# LCD.net
KiCad netlist of a schematic drawn in Altium Designer
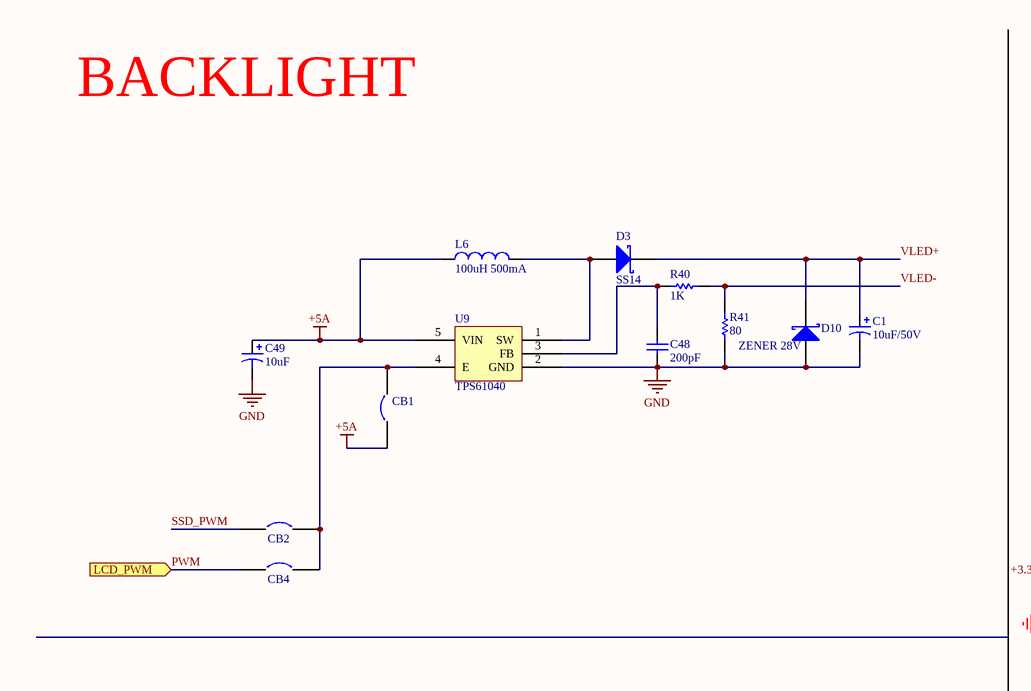
[diagram p0: LCD.SchDoc, left]
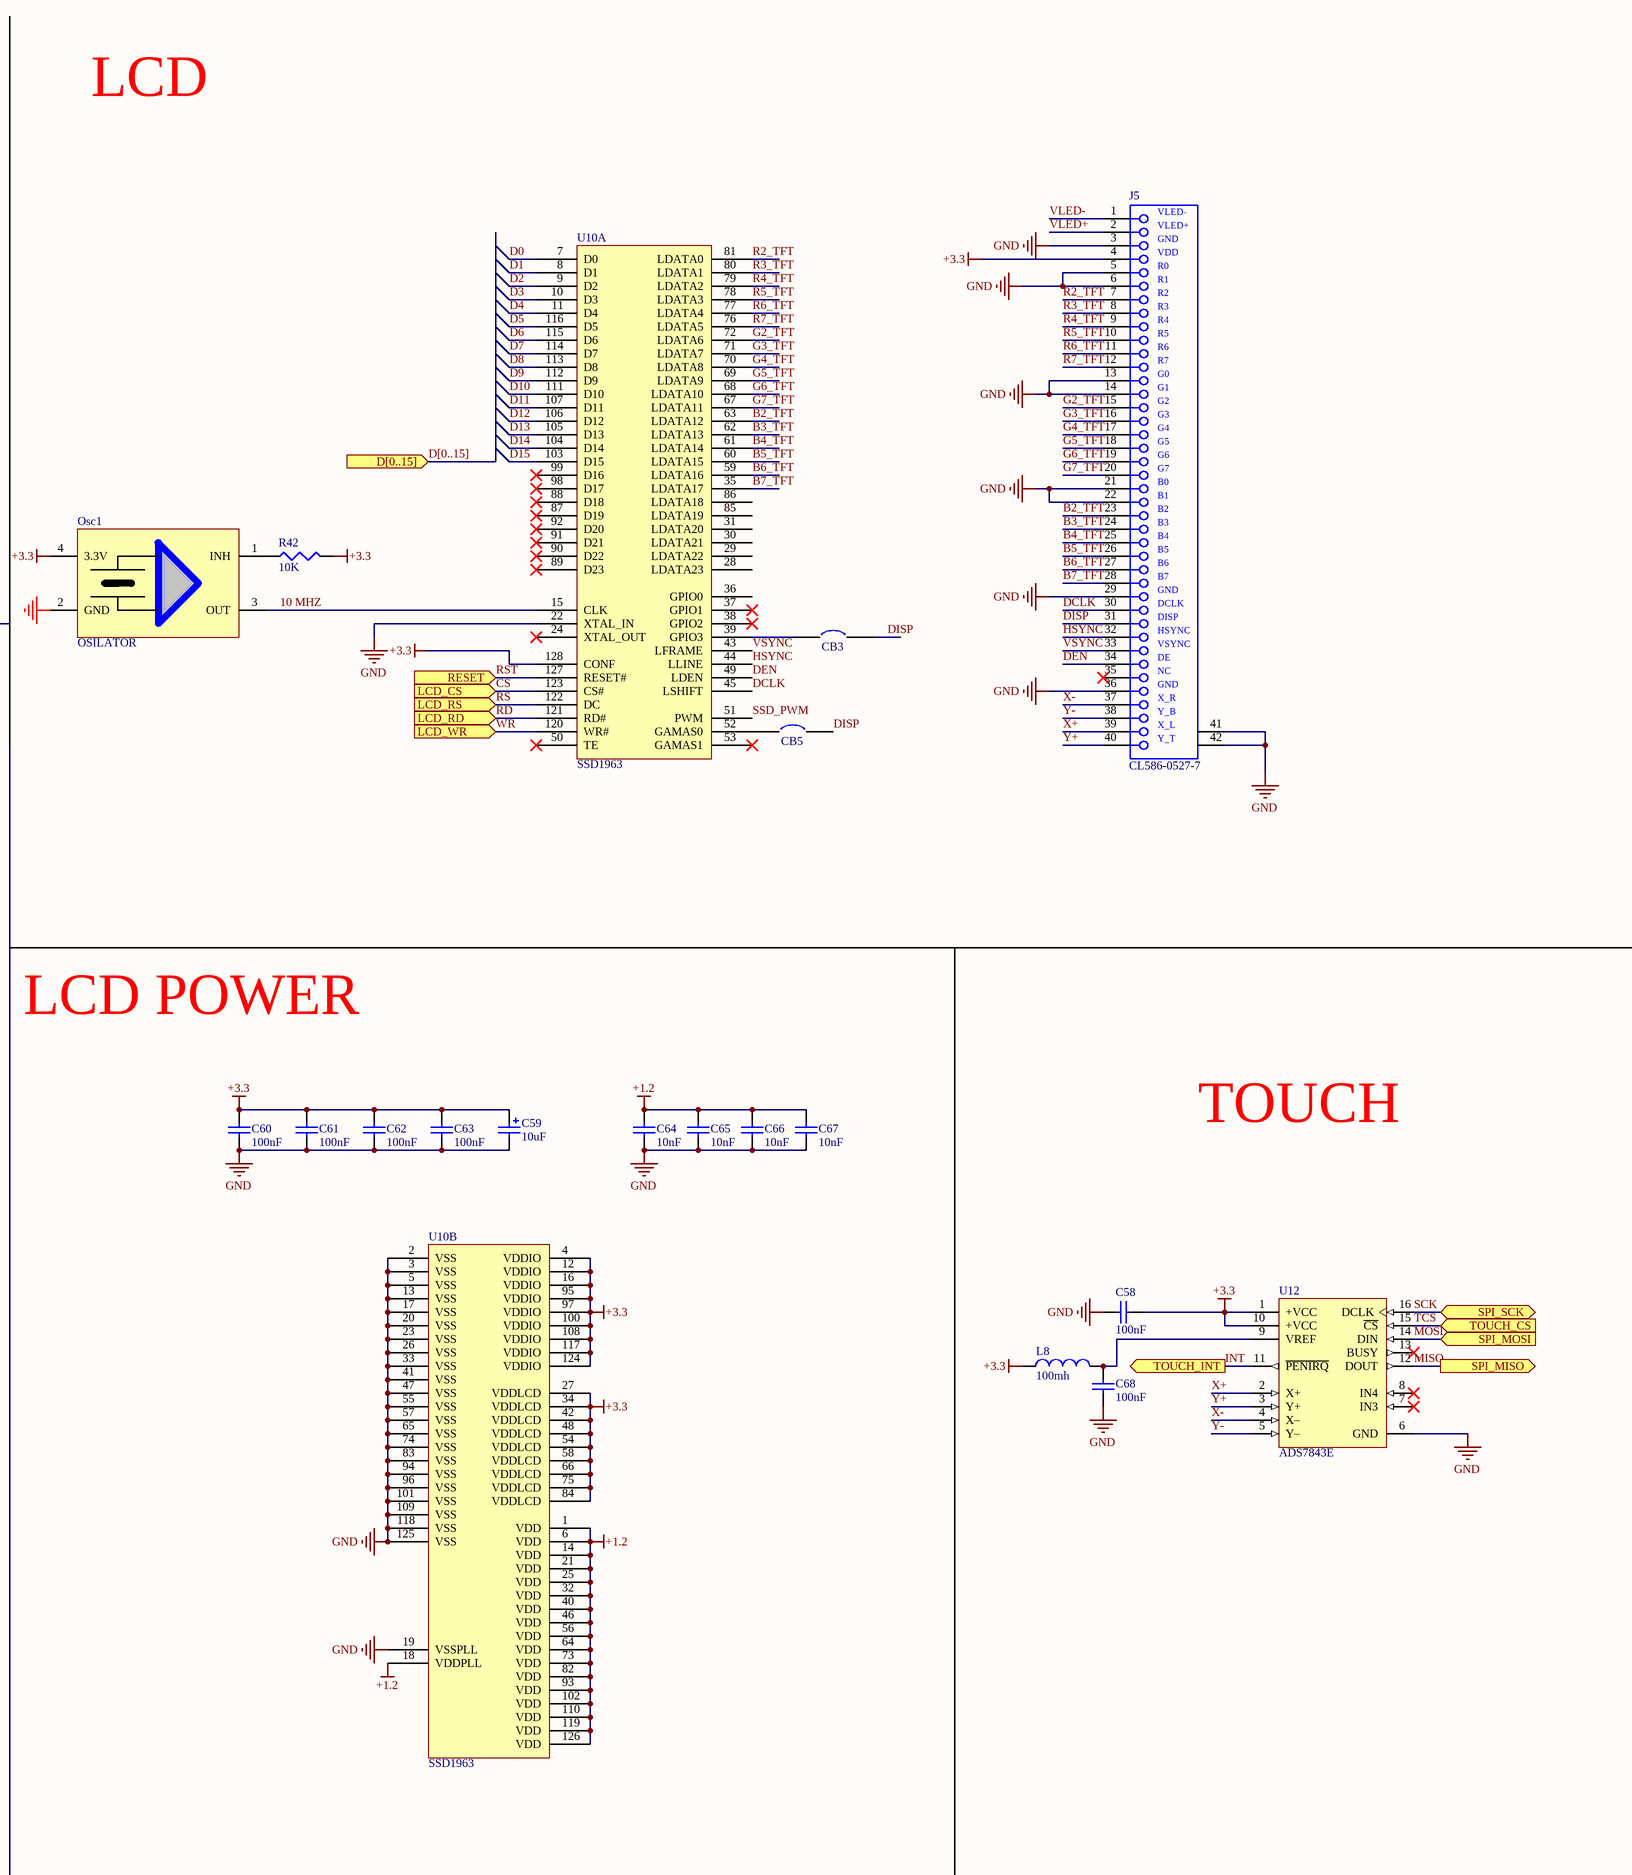
[diagram p1: LCD.SchDoc, right]

(export (version "E")
  (design (tool "Eeschema 10.0.6"))
  (components
    (comp (ref "C1")
      (value "10uF/50V")
      (footprint "CAP1050")
      (description "Polarized Capacitor (Radial)")
      (fields (field (name "PUBLISHER") "Altium Limited"))
      (libsource (lib "") (part "Cap Pol1_1"))
    )
    (comp (ref "C48")
      (value "200pF")
      (footprint "1206")
      (description "Capacitor (Semiconductor SIM Model)")
      (fields (field (name "PUBLISHER") "Altium Limited"))
      (libsource (lib "Miscellaneous Devices") (part "Cap Semi"))
    )
    (comp (ref "C49")
      (value "10uF")
      (footprint "CAP1016")
      (description "Polarized Capacitor (Radial)")
      (fields (field (name "PUBLISHER") "Altium Limited"))
      (libsource (lib "") (part "Cap Pol1_1"))
    )
    (comp (ref "C58")
      (value "100nF")
      (footprint "1206")
      (description "Capacitor")
      (fields (field (name "PUBLISHER") "Altium Limited"))
      (libsource (lib "Miscellaneous Devices") (part "Cap"))
    )
    (comp (ref "C59")
      (value "10uF")
      (footprint "CAP1016")
      (description "Polarized Capacitor (Radial)")
      (fields (field (name "PUBLISHER") "Altium Limited"))
      (libsource (lib "Miscellaneous Devices") (part "Cap Pol1"))
    )
    (comp (ref "C60")
      (value "100nF")
      (footprint "0805")
      (description "Capacitor")
      (fields (field (name "PUBLISHER") "Altium Limited"))
      (libsource (lib "Miscellaneous Devices") (part "Cap"))
    )
    (comp (ref "C61")
      (value "100nF")
      (footprint "0805")
      (description "Capacitor")
      (fields (field (name "PUBLISHER") "Altium Limited"))
      (libsource (lib "Miscellaneous Devices") (part "Cap"))
    )
    (comp (ref "C62")
      (value "100nF")
      (footprint "0805")
      (description "Capacitor")
      (fields (field (name "PUBLISHER") "Altium Limited"))
      (libsource (lib "Miscellaneous Devices") (part "Cap"))
    )
    (comp (ref "C63")
      (value "100nF")
      (footprint "0805")
      (description "Capacitor")
      (fields (field (name "PUBLISHER") "Altium Limited"))
      (libsource (lib "Miscellaneous Devices") (part "Cap"))
    )
    (comp (ref "C64")
      (value "10nF")
      (footprint "0805")
      (description "Capacitor")
      (fields (field (name "PUBLISHER") "Altium Limited"))
      (libsource (lib "Miscellaneous Devices") (part "Cap"))
    )
    (comp (ref "C65")
      (value "10nF")
      (footprint "0805")
      (description "Capacitor")
      (fields (field (name "PUBLISHER") "Altium Limited"))
      (libsource (lib "Miscellaneous Devices") (part "Cap"))
    )
    (comp (ref "C66")
      (value "10nF")
      (footprint "0805")
      (description "Capacitor")
      (fields (field (name "PUBLISHER") "Altium Limited"))
      (libsource (lib "Miscellaneous Devices") (part "Cap"))
    )
    (comp (ref "C67")
      (value "10nF")
      (footprint "0805")
      (description "Capacitor")
      (fields (field (name "PUBLISHER") "Altium Limited"))
      (libsource (lib "Miscellaneous Devices") (part "Cap"))
    )
    (comp (ref "C68")
      (value "100nF")
      (footprint "1206")
      (description "Capacitor")
      (fields (field (name "PUBLISHER") "Altium Limited"))
      (libsource (lib "Miscellaneous Devices") (part "Cap"))
    )
    (comp (ref "CB1")
      (value "JUMPER")
      (footprint "0805")
      (description "Circuit Breaker")
      (fields (field (name "PUBLISHER") "Altium Limited"))
      (libsource (lib "Miscellaneous Devices") (part "Circuit Breaker"))
    )
    (comp (ref "CB2")
      (value "JUMPER")
      (footprint "0805")
      (description "Circuit Breaker")
      (fields (field (name "PUBLISHER") "Altium Limited"))
      (libsource (lib "Miscellaneous Devices") (part "Circuit Breaker"))
    )
    (comp (ref "CB3")
      (value "JUMPER")
      (footprint "0805")
      (description "Circuit Breaker")
      (fields (field (name "PUBLISHER") "Altium Limited"))
      (libsource (lib "Miscellaneous Devices") (part "Circuit Breaker"))
    )
    (comp (ref "CB4")
      (value "JUMPER")
      (footprint "0805")
      (description "Circuit Breaker")
      (fields (field (name "PUBLISHER") "Altium Limited"))
      (libsource (lib "Miscellaneous Devices") (part "Circuit Breaker"))
    )
    (comp (ref "CB5")
      (value "JUMPER")
      (footprint "0805")
      (description "Circuit Breaker")
      (fields (field (name "PUBLISHER") "Altium Limited"))
      (libsource (lib "Miscellaneous Devices") (part "Circuit Breaker"))
    )
    (comp (ref "D3")
      (value "SS14")
      (footprint "1N4007")
      (description "Schottky Diode")
      (fields (field (name "PUBLISHER") "Altium Limited"))
      (libsource (lib "Miscellaneous Devices") (part "D Schottky"))
    )
    (comp (ref "D10")
      (value "ZENER 28V")
      (footprint "1N4007")
      (description "Schottky Diode")
      (fields (field (name "PUBLISHER") "Altium Limited"))
      (libsource (lib "Miscellaneous Devices") (part "D Schottky"))
    )
    (comp (ref "J5")
      (value "CL586-0527-7")
      (footprint "FH40SB")
      (description "FH12 Series, \"Flip-Lock\" SMT/ZIF FFC/FPC Connector - 0.5mm Spaced Bottom Contact")
      (fields (field (name "PUBLISHER") "Altium Limited"))
      (libsource (lib "Schlib1") (part "CL586-0527-7"))
    )
    (comp (ref "L6")
      (value "100uH 500mA")
      (footprint "Inductorsmd")
      (description "Inductor")
      (fields (field (name "PUBLISHER") "Altium Limited"))
      (libsource (lib "Miscellaneous Devices") (part "Inductor"))
    )
    (comp (ref "L8")
      (value "100mh")
      (footprint "L1206")
      (description "Inductor")
      (fields (field (name "PUBLISHER") "Altium Limited"))
      (libsource (lib "Miscellaneous Devices") (part "Inductor"))
    )
    (comp (ref "Osc1")
      (value "OSILATOR")
      (footprint "XTAL_5X7")
      (libsource (lib "New Lib") (part "OSILATOR"))
    )
    (comp (ref "R40")
      (value "1K")
      (footprint "1206")
      (description "Resistor")
      (fields (field (name "PUBLISHER") "Altium Limited"))
      (libsource (lib "Miscellaneous Devices") (part "Res1"))
    )
    (comp (ref "R41")
      (value "80")
      (footprint "1206")
      (description "Resistor")
      (fields (field (name "PUBLISHER") "Altium Limited"))
      (libsource (lib "Miscellaneous Devices") (part "Res1"))
    )
    (comp (ref "R42")
      (value "10K")
      (footprint "1206")
      (description "Resistor")
      (fields (field (name "PUBLISHER") "Altium Limited"))
      (libsource (lib "Miscellaneous Devices") (part "Res3"))
    )
    (comp (ref "U9")
      (value "TPS61040")
      (footprint "SOT-23-5L")
      (description "Backlight Regulagtor")
      (libsource (lib "Schlib1") (part "TPS61040"))
    )
    (comp (ref "U10") (value "SSD1963") (footprint "LQFP128_M") (libsource (lib "Schlib1") (part "SSD1963")))
    (comp (ref "U12")
      (value "ADS7843E")
      (footprint "DBQ016")
      (description "4-Wire Touch Screen Controller, 16-Pin SSOP, Pb-Free")
      (fields (field (name "PUBLISHER") "Altium Limited"))
      (libsource (lib "TI Interface Touch Screen Controller") (part "ADS7843E"))
    )
  )
  (nets
    (net (code "1") (name "+1.2") (class "Default")
      (node (ref "C64") (pin "1") (pinfunction "1_1") (pintype "passive"))
      (node (ref "C65") (pin "1") (pinfunction "1_1") (pintype "passive"))
      (node (ref "C66") (pin "1") (pinfunction "1_1") (pintype "passive"))
      (node (ref "C67") (pin "1") (pinfunction "1_1") (pintype "passive"))
      (node (ref "U10") (pin "1") (pinfunction "VDD_1") (pintype "power_in"))
      (node (ref "U10") (pin "102") (pinfunction "VDD_102") (pintype "power_in"))
      (node (ref "U10") (pin "110") (pinfunction "VDD_110") (pintype "power_in"))
      (node (ref "U10") (pin "119") (pinfunction "VDD_119") (pintype "power_in"))
      (node (ref "U10") (pin "126") (pinfunction "VDD_126") (pintype "power_in"))
      (node (ref "U10") (pin "14") (pinfunction "VDD_14") (pintype "power_in"))
      (node (ref "U10") (pin "18") (pinfunction "VDDPLL_18") (pintype "power_in"))
      (node (ref "U10") (pin "21") (pinfunction "VDD_21") (pintype "power_in"))
      (node (ref "U10") (pin "25") (pinfunction "VDD_25") (pintype "power_in"))
      (node (ref "U10") (pin "32") (pinfunction "VDD_32") (pintype "power_in"))
      (node (ref "U10") (pin "40") (pinfunction "VDD_40") (pintype "power_in"))
      (node (ref "U10") (pin "46") (pinfunction "VDD_46") (pintype "power_in"))
      (node (ref "U10") (pin "56") (pinfunction "VDD_56") (pintype "power_in"))
      (node (ref "U10") (pin "6") (pinfunction "VDD_6") (pintype "power_in"))
      (node (ref "U10") (pin "64") (pinfunction "VDD_64") (pintype "power_in"))
      (node (ref "U10") (pin "73") (pinfunction "VDD_73") (pintype "power_in"))
      (node (ref "U10") (pin "82") (pinfunction "VDD_82") (pintype "power_in"))
      (node (ref "U10") (pin "93") (pinfunction "VDD_93") (pintype "power_in"))
    )
    (net (code "2") (name "+3.3") (class "Default")
      (node (ref "C58") (pin "2") (pinfunction "2_2") (pintype "passive"))
      (node (ref "C59") (pin "1") (pinfunction "1_1") (pintype "passive"))
      (node (ref "C60") (pin "1") (pinfunction "1_1") (pintype "passive"))
      (node (ref "C61") (pin "1") (pinfunction "1_1") (pintype "passive"))
      (node (ref "C62") (pin "1") (pinfunction "1_1") (pintype "passive"))
      (node (ref "C63") (pin "1") (pinfunction "1_1") (pintype "passive"))
      (node (ref "J5") (pin "4") (pinfunction "4_4") (pintype "passive"))
      (node (ref "L8") (pin "1") (pinfunction "1_1") (pintype "passive"))
      (node (ref "Osc1") (pin "4") (pinfunction "3.3V_4") (pintype "passive"))
      (node (ref "R42") (pin "2") (pinfunction "2_2") (pintype "passive"))
      (node (ref "U10") (pin "100") (pinfunction "VDDIO_100") (pintype "power_in"))
      (node (ref "U10") (pin "108") (pinfunction "VDDIO_108") (pintype "power_in"))
      (node (ref "U10") (pin "117") (pinfunction "VDDIO_117") (pintype "power_in"))
      (node (ref "U10") (pin "12") (pinfunction "VDDIO_12") (pintype "power_in"))
      (node (ref "U10") (pin "124") (pinfunction "VDDIO_124") (pintype "power_in"))
      (node (ref "U10") (pin "128") (pinfunction "CONF_128") (pintype "passive"))
      (node (ref "U10") (pin "16") (pinfunction "VDDIO_16") (pintype "power_in"))
      (node (ref "U10") (pin "27") (pinfunction "VDDLCD_27") (pintype "power_in"))
      (node (ref "U10") (pin "34") (pinfunction "VDDLCD_34") (pintype "power_in"))
      (node (ref "U10") (pin "4") (pinfunction "VDDIO_4") (pintype "power_in"))
      (node (ref "U10") (pin "42") (pinfunction "VDDLCD_42") (pintype "power_in"))
      (node (ref "U10") (pin "48") (pinfunction "VDDLCD_48") (pintype "power_in"))
      (node (ref "U10") (pin "54") (pinfunction "VDDLCD_54") (pintype "power_in"))
      (node (ref "U10") (pin "58") (pinfunction "VDDLCD_58") (pintype "power_in"))
      (node (ref "U10") (pin "66") (pinfunction "VDDLCD_66") (pintype "power_in"))
      (node (ref "U10") (pin "75") (pinfunction "VDDLCD_75") (pintype "power_in"))
      (node (ref "U10") (pin "84") (pinfunction "VDDLCD_84") (pintype "power_in"))
      (node (ref "U10") (pin "95") (pinfunction "VDDIO_95") (pintype "power_in"))
      (node (ref "U10") (pin "97") (pinfunction "VDDIO_97") (pintype "power_in"))
      (node (ref "U12") (pin "1") (pinfunction "+VCC_1") (pintype "power_in"))
      (node (ref "U12") (pin "10") (pinfunction "+VCC_10") (pintype "power_in"))
    )
    (net (code "3") (name "+5A") (class "Default")
      (node (ref "C49") (pin "1") (pinfunction "1_1") (pintype "passive"))
      (node (ref "CB1") (pin "1") (pinfunction "1_1") (pintype "passive"))
      (node (ref "L6") (pin "1") (pinfunction "1_1") (pintype "passive"))
      (node (ref "U9") (pin "5") (pinfunction "VIN_5") (pintype "passive"))
    )
    (net (code "4") (name "/10 MHZ") (class "Default")
      (node (ref "Osc1") (pin "3") (pinfunction "OUT_3") (pintype "passive"))
      (node (ref "U10") (pin "15") (pinfunction "CLK_15") (pintype "power_in"))
    )
    (net (code "5") (name "/B2_TFT") (class "Default")
      (node (ref "J5") (pin "23") (pinfunction "23_23") (pintype "passive"))
      (node (ref "U10") (pin "63") (pinfunction "LDATA12_63") (pintype "power_in"))
    )
    (net (code "6") (name "/B3_TFT") (class "Default")
      (node (ref "J5") (pin "24") (pinfunction "24_24") (pintype "passive"))
      (node (ref "U10") (pin "62") (pinfunction "LDATA13_62") (pintype "power_in"))
    )
    (net (code "7") (name "/B4_TFT") (class "Default")
      (node (ref "J5") (pin "25") (pinfunction "25_25") (pintype "passive"))
      (node (ref "U10") (pin "61") (pinfunction "LDATA14_61") (pintype "power_in"))
    )
    (net (code "8") (name "/B5_TFT") (class "Default")
      (node (ref "J5") (pin "26") (pinfunction "26_26") (pintype "passive"))
      (node (ref "U10") (pin "60") (pinfunction "LDATA15_60") (pintype "power_in"))
    )
    (net (code "9") (name "/B6_TFT") (class "Default")
      (node (ref "J5") (pin "27") (pinfunction "27_27") (pintype "passive"))
      (node (ref "U10") (pin "59") (pinfunction "LDATA16_59") (pintype "power_in"))
    )
    (net (code "10") (name "/B7_TFT") (class "Default")
      (node (ref "J5") (pin "28") (pinfunction "28_28") (pintype "passive"))
      (node (ref "U10") (pin "35") (pinfunction "LDATA17_35") (pintype "power_in"))
    )
    (net (code "11") (name "/CS") (class "Default")
      (node (ref "U10") (pin "123") (pinfunction "CS#_123") (pintype "passive"))
    )
    (net (code "12") (name "/D0") (class "Default")
      (node (ref "U10") (pin "7") (pinfunction "D0_7") (pintype "power_in"))
    )
    (net (code "13") (name "/D1") (class "Default")
      (node (ref "U10") (pin "8") (pinfunction "D1_8") (pintype "power_in"))
    )
    (net (code "14") (name "/D2") (class "Default")
      (node (ref "U10") (pin "9") (pinfunction "D2_9") (pintype "power_in"))
    )
    (net (code "15") (name "/D3") (class "Default")
      (node (ref "U10") (pin "10") (pinfunction "D3_10") (pintype "power_in"))
    )
    (net (code "16") (name "/D4") (class "Default")
      (node (ref "U10") (pin "11") (pinfunction "D4_11") (pintype "power_in"))
    )
    (net (code "17") (name "/D5") (class "Default")
      (node (ref "U10") (pin "116") (pinfunction "D5_116") (pintype "power_in"))
    )
    (net (code "18") (name "/D6") (class "Default")
      (node (ref "U10") (pin "115") (pinfunction "D6_115") (pintype "power_in"))
    )
    (net (code "19") (name "/D7") (class "Default")
      (node (ref "U10") (pin "114") (pinfunction "D7_114") (pintype "power_in"))
    )
    (net (code "20") (name "/D8") (class "Default")
      (node (ref "U10") (pin "113") (pinfunction "D8_113") (pintype "power_in"))
    )
    (net (code "21") (name "/D9") (class "Default")
      (node (ref "U10") (pin "112") (pinfunction "D9_112") (pintype "power_in"))
    )
    (net (code "22") (name "/D10") (class "Default")
      (node (ref "U10") (pin "111") (pinfunction "D10_111") (pintype "power_in"))
    )
    (net (code "23") (name "/D11") (class "Default")
      (node (ref "U10") (pin "107") (pinfunction "D11_107") (pintype "power_in"))
    )
    (net (code "24") (name "/D12") (class "Default")
      (node (ref "U10") (pin "106") (pinfunction "D12_106") (pintype "power_in"))
    )
    (net (code "25") (name "/D13") (class "Default")
      (node (ref "U10") (pin "105") (pinfunction "D13_105") (pintype "power_in"))
    )
    (net (code "26") (name "/D14") (class "Default")
      (node (ref "U10") (pin "104") (pinfunction "D14_104") (pintype "power_in"))
    )
    (net (code "27") (name "/D15") (class "Default")
      (node (ref "U10") (pin "103") (pinfunction "D15_103") (pintype "power_in"))
    )
    (net (code "28") (name "/DCLK") (class "Default")
      (node (ref "J5") (pin "30") (pinfunction "30_30") (pintype "passive"))
      (node (ref "U10") (pin "45") (pinfunction "LSHIFT_45") (pintype "power_in"))
    )
    (net (code "29") (name "/DEN") (class "Default")
      (node (ref "J5") (pin "34") (pinfunction "34_34") (pintype "passive"))
      (node (ref "U10") (pin "49") (pinfunction "LDEN_49") (pintype "power_in"))
    )
    (net (code "30") (name "/DISP") (class "Default")
      (node (ref "CB3") (pin "2") (pinfunction "2_2") (pintype "passive"))
      (node (ref "CB5") (pin "2") (pinfunction "2_2") (pintype "passive"))
      (node (ref "J5") (pin "31") (pinfunction "31_31") (pintype "passive"))
    )
    (net (code "32") (name "/G2_TFT") (class "Default")
      (node (ref "J5") (pin "15") (pinfunction "15_15") (pintype "passive"))
      (node (ref "U10") (pin "72") (pinfunction "LDATA6_72") (pintype "power_in"))
    )
    (net (code "33") (name "/G3_TFT") (class "Default")
      (node (ref "J5") (pin "16") (pinfunction "16_16") (pintype "passive"))
      (node (ref "U10") (pin "71") (pinfunction "LDATA7_71") (pintype "power_in"))
    )
    (net (code "34") (name "/G4_TFT") (class "Default")
      (node (ref "J5") (pin "17") (pinfunction "17_17") (pintype "passive"))
      (node (ref "U10") (pin "70") (pinfunction "LDATA8_70") (pintype "power_in"))
    )
    (net (code "35") (name "/G5_TFT") (class "Default")
      (node (ref "J5") (pin "18") (pinfunction "18_18") (pintype "passive"))
      (node (ref "U10") (pin "69") (pinfunction "LDATA9_69") (pintype "power_in"))
    )
    (net (code "36") (name "/G6_TFT") (class "Default")
      (node (ref "J5") (pin "19") (pinfunction "19_19") (pintype "passive"))
      (node (ref "U10") (pin "68") (pinfunction "LDATA10_68") (pintype "power_in"))
    )
    (net (code "37") (name "/G7_TFT") (class "Default")
      (node (ref "J5") (pin "20") (pinfunction "20_20") (pintype "passive"))
      (node (ref "U10") (pin "67") (pinfunction "LDATA11_67") (pintype "power_in"))
    )
    (net (code "38") (name "/HSYNC") (class "Default")
      (node (ref "J5") (pin "32") (pinfunction "32_32") (pintype "passive"))
      (node (ref "U10") (pin "44") (pinfunction "LLINE_44") (pintype "power_in"))
    )
    (net (code "39") (name "/INT") (class "Default")
      (node (ref "U12") (pin "11") (pinfunction "~{PENIRQ}_11") (pintype "output"))
    )
    (net (code "40") (name "/MISO") (class "Default")
      (node (ref "U12") (pin "12") (pinfunction "DOUT_12") (pintype "output"))
    )
    (net (code "41") (name "/MOSI") (class "Default")
      (node (ref "U12") (pin "14") (pinfunction "DIN_14") (pintype "input"))
    )
    (net (code "42") (name "/PWM") (class "Default")
      (node (ref "CB4") (pin "1") (pinfunction "1_1") (pintype "passive"))
    )
    (net (code "43") (name "/R2_TFT") (class "Default")
      (node (ref "J5") (pin "7") (pinfunction "7_7") (pintype "passive"))
      (node (ref "U10") (pin "81") (pinfunction "LDATA0_81") (pintype "power_in"))
    )
    (net (code "44") (name "/R3_TFT") (class "Default")
      (node (ref "J5") (pin "8") (pinfunction "8_8") (pintype "passive"))
      (node (ref "U10") (pin "80") (pinfunction "LDATA1_80") (pintype "power_in"))
    )
    (net (code "45") (name "/R4_TFT") (class "Default")
      (node (ref "J5") (pin "9") (pinfunction "9_9") (pintype "passive"))
      (node (ref "U10") (pin "79") (pinfunction "LDATA2_79") (pintype "power_in"))
    )
    (net (code "46") (name "/R5_TFT") (class "Default")
      (node (ref "J5") (pin "10") (pinfunction "10_10") (pintype "passive"))
      (node (ref "U10") (pin "78") (pinfunction "LDATA3_78") (pintype "power_in"))
    )
    (net (code "47") (name "/R6_TFT") (class "Default")
      (node (ref "J5") (pin "11") (pinfunction "11_11") (pintype "passive"))
      (node (ref "U10") (pin "77") (pinfunction "LDATA4_77") (pintype "power_in"))
    )
    (net (code "48") (name "/R7_TFT") (class "Default")
      (node (ref "J5") (pin "12") (pinfunction "12_12") (pintype "passive"))
      (node (ref "U10") (pin "76") (pinfunction "LDATA5_76") (pintype "power_in"))
    )
    (net (code "49") (name "/RD") (class "Default")
      (node (ref "U10") (pin "121") (pinfunction "RD#_121") (pintype "passive"))
    )
    (net (code "50") (name "/RS") (class "Default")
      (node (ref "U10") (pin "122") (pinfunction "DC_122") (pintype "passive"))
    )
    (net (code "51") (name "/RST") (class "Default")
      (node (ref "U10") (pin "127") (pinfunction "RESET#_127") (pintype "passive"))
    )
    (net (code "52") (name "/SCK") (class "Default")
      (node (ref "U12") (pin "16") (pinfunction "DCLK_16") (pintype "input"))
    )
    (net (code "53") (name "/SSD_PWM") (class "Default")
      (node (ref "CB2") (pin "1") (pinfunction "1_1") (pintype "passive"))
      (node (ref "U10") (pin "51") (pinfunction "PWM_51") (pintype "power_in"))
    )
    (net (code "54") (name "/TCS") (class "Default")
      (node (ref "U12") (pin "15") (pinfunction "~{CS}_15") (pintype "input"))
    )
    (net (code "55") (name "/VLED+") (class "Default")
      (node (ref "C1") (pin "1") (pinfunction "1_1") (pintype "passive"))
      (node (ref "D10") (pin "2") (pinfunction "K_2") (pintype "passive"))
      (node (ref "D3") (pin "2") (pinfunction "K_2") (pintype "passive"))
      (node (ref "J5") (pin "2") (pinfunction "2_2") (pintype "passive"))
    )
    (net (code "56") (name "/VLED-") (class "Default")
      (node (ref "J5") (pin "1") (pinfunction "1_1") (pintype "passive"))
      (node (ref "R40") (pin "2") (pinfunction "2_2") (pintype "passive"))
      (node (ref "R41") (pin "2") (pinfunction "2_2") (pintype "passive"))
    )
    (net (code "57") (name "/VSYNC") (class "Default")
      (node (ref "J5") (pin "33") (pinfunction "33_33") (pintype "passive"))
      (node (ref "U10") (pin "43") (pinfunction "LFRAME_43") (pintype "power_in"))
    )
    (net (code "58") (name "/WR") (class "Default")
      (node (ref "U10") (pin "120") (pinfunction "WR#_120") (pintype "passive"))
    )
    (net (code "59") (name "/X+") (class "Default")
      (node (ref "J5") (pin "39") (pinfunction "39_39") (pintype "passive"))
      (node (ref "U12") (pin "2") (pinfunction "X+_2") (pintype "input"))
    )
    (net (code "60") (name "/X-") (class "Default")
      (node (ref "J5") (pin "37") (pinfunction "37_37") (pintype "passive"))
      (node (ref "U12") (pin "4") (pinfunction "X_4") (pintype "input"))
    )
    (net (code "61") (name "/Y+") (class "Default")
      (node (ref "J5") (pin "40") (pinfunction "40_40") (pintype "passive"))
      (node (ref "U12") (pin "3") (pinfunction "Y+_3") (pintype "input"))
    )
    (net (code "62") (name "/Y-") (class "Default")
      (node (ref "J5") (pin "38") (pinfunction "38_38") (pintype "passive"))
      (node (ref "U12") (pin "5") (pinfunction "Y_5") (pintype "input"))
    )
    (net (code "63") (name "GND") (class "Default")
      (node (ref "C1") (pin "2") (pinfunction "2_2") (pintype "passive"))
      (node (ref "C48") (pin "1") (pinfunction "1_1") (pintype "passive"))
      (node (ref "C49") (pin "2") (pinfunction "2_2") (pintype "passive"))
      (node (ref "C58") (pin "1") (pinfunction "1_1") (pintype "passive"))
      (node (ref "C59") (pin "2") (pinfunction "2_2") (pintype "passive"))
      (node (ref "C60") (pin "2") (pinfunction "2_2") (pintype "passive"))
      (node (ref "C61") (pin "2") (pinfunction "2_2") (pintype "passive"))
      (node (ref "C62") (pin "2") (pinfunction "2_2") (pintype "passive"))
      (node (ref "C63") (pin "2") (pinfunction "2_2") (pintype "passive"))
      (node (ref "C64") (pin "2") (pinfunction "2_2") (pintype "passive"))
      (node (ref "C65") (pin "2") (pinfunction "2_2") (pintype "passive"))
      (node (ref "C66") (pin "2") (pinfunction "2_2") (pintype "passive"))
      (node (ref "C67") (pin "2") (pinfunction "2_2") (pintype "passive"))
      (node (ref "C68") (pin "1") (pinfunction "1_1") (pintype "passive"))
      (node (ref "D10") (pin "1") (pinfunction "A_1") (pintype "passive"))
      (node (ref "J5") (pin "13") (pinfunction "13_13") (pintype "passive"))
      (node (ref "J5") (pin "14") (pinfunction "14_14") (pintype "passive"))
      (node (ref "J5") (pin "21") (pinfunction "21_21") (pintype "passive"))
      (node (ref "J5") (pin "22") (pinfunction "22_22") (pintype "passive"))
      (node (ref "J5") (pin "29") (pinfunction "29_29") (pintype "passive"))
      (node (ref "J5") (pin "3") (pinfunction "3_3") (pintype "passive"))
      (node (ref "J5") (pin "36") (pinfunction "36_36") (pintype "passive"))
      (node (ref "J5") (pin "41") (pinfunction "MH1_41") (pintype "passive"))
      (node (ref "J5") (pin "42") (pinfunction "MH2_42") (pintype "passive"))
      (node (ref "J5") (pin "5") (pinfunction "5_5") (pintype "passive"))
      (node (ref "J5") (pin "6") (pinfunction "6_6") (pintype "passive"))
      (node (ref "Osc1") (pin "2") (pinfunction "GND_2") (pintype "passive"))
      (node (ref "R41") (pin "1") (pinfunction "1_1") (pintype "passive"))
      (node (ref "U10") (pin "101") (pinfunction "VSS_101") (pintype "power_in"))
      (node (ref "U10") (pin "109") (pinfunction "VSS_109") (pintype "power_in"))
      (node (ref "U10") (pin "118") (pinfunction "VSS_118") (pintype "power_in"))
      (node (ref "U10") (pin "125") (pinfunction "VSS_125") (pintype "power_in"))
      (node (ref "U10") (pin "13") (pinfunction "VSS_13") (pintype "power_in"))
      (node (ref "U10") (pin "17") (pinfunction "VSS_17") (pintype "power_in"))
      (node (ref "U10") (pin "19") (pinfunction "VSSPLL_19") (pintype "power_in"))
      (node (ref "U10") (pin "2") (pinfunction "VSS_2") (pintype "power_in"))
      (node (ref "U10") (pin "20") (pinfunction "VSS_20") (pintype "power_in"))
      (node (ref "U10") (pin "22") (pinfunction "XTAL_IN_22") (pintype "power_in"))
      (node (ref "U10") (pin "23") (pinfunction "VSS_23") (pintype "power_in"))
      (node (ref "U10") (pin "26") (pinfunction "VSS_26") (pintype "power_in"))
      (node (ref "U10") (pin "3") (pinfunction "VSS_3") (pintype "power_in"))
      (node (ref "U10") (pin "33") (pinfunction "VSS_33") (pintype "power_in"))
      (node (ref "U10") (pin "41") (pinfunction "VSS_41") (pintype "power_in"))
      (node (ref "U10") (pin "47") (pinfunction "VSS_47") (pintype "power_in"))
      (node (ref "U10") (pin "5") (pinfunction "VSS_5") (pintype "power_in"))
      (node (ref "U10") (pin "55") (pinfunction "VSS_55") (pintype "power_in"))
      (node (ref "U10") (pin "57") (pinfunction "VSS_57") (pintype "power_in"))
      (node (ref "U10") (pin "65") (pinfunction "VSS_65") (pintype "power_in"))
      (node (ref "U10") (pin "74") (pinfunction "VSS_74") (pintype "power_in"))
      (node (ref "U10") (pin "83") (pinfunction "VSS_83") (pintype "power_in"))
      (node (ref "U10") (pin "94") (pinfunction "VSS_94") (pintype "power_in"))
      (node (ref "U10") (pin "96") (pinfunction "VSS_96") (pintype "power_in"))
      (node (ref "U12") (pin "6") (pinfunction "GND_6") (pintype "power_in"))
      (node (ref "U9") (pin "2") (pinfunction "GND_2") (pintype "passive"))
    )
    (net (code "64") (name "Net-(D3-A)") (class "Default")
      (node (ref "D3") (pin "1") (pinfunction "A_1") (pintype "passive"))
      (node (ref "L6") (pin "2") (pinfunction "2_2") (pintype "passive"))
      (node (ref "U9") (pin "1") (pinfunction "SW_1") (pintype "passive"))
    )
    (net (code "65") (name "Net-(Osc1-INH)") (class "Default")
      (node (ref "Osc1") (pin "1") (pinfunction "INH_1") (pintype "passive"))
      (node (ref "R42") (pin "1") (pinfunction "1_1") (pintype "passive"))
    )
    (net (code "66") (name "Net-(U9-E)") (class "Default")
      (node (ref "CB1") (pin "2") (pinfunction "2_2") (pintype "passive"))
      (node (ref "CB2") (pin "2") (pinfunction "2_2") (pintype "passive"))
      (node (ref "CB4") (pin "2") (pinfunction "2_2") (pintype "passive"))
      (node (ref "U9") (pin "4") (pinfunction "E_4") (pintype "passive"))
    )
    (net (code "67") (name "Net-(U9-FB)") (class "Default")
      (node (ref "C48") (pin "2") (pinfunction "2_2") (pintype "passive"))
      (node (ref "R40") (pin "1") (pinfunction "1_1") (pintype "passive"))
      (node (ref "U9") (pin "3") (pinfunction "FB_3") (pintype "passive"))
    )
    (net (code "68") (name "Net-(U10A-GAMAS0)") (class "Default")
      (node (ref "CB5") (pin "1") (pinfunction "1_1") (pintype "passive"))
      (node (ref "U10") (pin "52") (pinfunction "GAMAS0_52") (pintype "power_in"))
    )
    (net (code "69") (name "Net-(U10A-GPIO3)") (class "Default")
      (node (ref "CB3") (pin "1") (pinfunction "1_1") (pintype "passive"))
      (node (ref "U10") (pin "39") (pinfunction "GPIO3_39") (pintype "power_in"))
    )
    (net (code "70") (name "Net-(U12-VREF)") (class "Default")
      (node (ref "C68") (pin "2") (pinfunction "2_2") (pintype "passive"))
      (node (ref "L8") (pin "2") (pinfunction "2_2") (pintype "passive"))
      (node (ref "U12") (pin "9") (pinfunction "VREF_9") (pintype "power_in"))
    )
    (net (code "71") (name "unconnected-(J5-Pad35)") (class "Default")
      (node (ref "J5") (pin "35") (pinfunction "35_35") (pintype "passive+no_connect"))
    )
    (net (code "72") (name "unconnected-(U10A-D16-Pad99)") (class "Default")
      (node (ref "U10") (pin "99") (pinfunction "D16_99") (pintype "power_in+no_connect"))
    )
    (net (code "73") (name "unconnected-(U10A-D17-Pad98)") (class "Default")
      (node (ref "U10") (pin "98") (pinfunction "D17_98") (pintype "power_in+no_connect"))
    )
    (net (code "74") (name "unconnected-(U10A-D18-Pad88)") (class "Default")
      (node (ref "U10") (pin "88") (pinfunction "D18_88") (pintype "power_in+no_connect"))
    )
    (net (code "75") (name "unconnected-(U10A-D19-Pad87)") (class "Default")
      (node (ref "U10") (pin "87") (pinfunction "D19_87") (pintype "power_in+no_connect"))
    )
    (net (code "76") (name "unconnected-(U10A-D20-Pad92)") (class "Default")
      (node (ref "U10") (pin "92") (pinfunction "D20_92") (pintype "power_in+no_connect"))
    )
    (net (code "77") (name "unconnected-(U10A-D21-Pad91)") (class "Default")
      (node (ref "U10") (pin "91") (pinfunction "D21_91") (pintype "power_in+no_connect"))
    )
    (net (code "78") (name "unconnected-(U10A-D22-Pad90)") (class "Default")
      (node (ref "U10") (pin "90") (pinfunction "D22_90") (pintype "power_in+no_connect"))
    )
    (net (code "79") (name "unconnected-(U10A-D23-Pad89)") (class "Default")
      (node (ref "U10") (pin "89") (pinfunction "D23_89") (pintype "power_in+no_connect"))
    )
    (net (code "80") (name "unconnected-(U10A-GAMAS1-Pad53)") (class "Default")
      (node (ref "U10") (pin "53") (pinfunction "GAMAS1_53") (pintype "power_in+no_connect"))
    )
    (net (code "81") (name "unconnected-(U10A-GPIO0-Pad36)") (class "Default")
      (node (ref "U10") (pin "36") (pinfunction "GPIO0_36") (pintype "power_in"))
    )
    (net (code "82") (name "unconnected-(U10A-GPIO1-Pad37)") (class "Default")
      (node (ref "U10") (pin "37") (pinfunction "GPIO1_37") (pintype "power_in+no_connect"))
    )
    (net (code "83") (name "unconnected-(U10A-GPIO2-Pad38)") (class "Default")
      (node (ref "U10") (pin "38") (pinfunction "GPIO2_38") (pintype "power_in+no_connect"))
    )
    (net (code "84") (name "unconnected-(U10A-LDATA18-Pad86)") (class "Default")
      (node (ref "U10") (pin "86") (pinfunction "LDATA18_86") (pintype "power_in"))
    )
    (net (code "85") (name "unconnected-(U10A-LDATA19-Pad85)") (class "Default")
      (node (ref "U10") (pin "85") (pinfunction "LDATA19_85") (pintype "power_in"))
    )
    (net (code "86") (name "unconnected-(U10A-LDATA20-Pad31)") (class "Default")
      (node (ref "U10") (pin "31") (pinfunction "LDATA20_31") (pintype "power_in"))
    )
    (net (code "87") (name "unconnected-(U10A-LDATA21-Pad30)") (class "Default")
      (node (ref "U10") (pin "30") (pinfunction "LDATA21_30") (pintype "power_in"))
    )
    (net (code "88") (name "unconnected-(U10A-LDATA22-Pad29)") (class "Default")
      (node (ref "U10") (pin "29") (pinfunction "LDATA22_29") (pintype "power_in"))
    )
    (net (code "89") (name "unconnected-(U10A-LDATA23-Pad28)") (class "Default")
      (node (ref "U10") (pin "28") (pinfunction "LDATA23_28") (pintype "power_in"))
    )
    (net (code "90") (name "unconnected-(U10A-TE-Pad50)") (class "Default")
      (node (ref "U10") (pin "50") (pinfunction "TE_50") (pintype "passive+no_connect"))
    )
    (net (code "91") (name "unconnected-(U10A-XTAL_OUT-Pad24)") (class "Default")
      (node (ref "U10") (pin "24") (pinfunction "XTAL_OUT_24") (pintype "power_in+no_connect"))
    )
    (net (code "92") (name "unconnected-(U12-BUSY-Pad13)") (class "Default")
      (node (ref "U12") (pin "13") (pinfunction "BUSY_13") (pintype "output+no_connect"))
    )
    (net (code "93") (name "unconnected-(U12-IN3-Pad7)") (class "Default")
      (node (ref "U12") (pin "7") (pinfunction "IN3_7") (pintype "input+no_connect"))
    )
    (net (code "94") (name "unconnected-(U12-IN4-Pad8)") (class "Default")
      (node (ref "U12") (pin "8") (pinfunction "IN4_8") (pintype "input+no_connect"))
    )
  )
)
